# AltiumFirst_STM32.net
KiCad netlist of a schematic drawn in Altium Designer
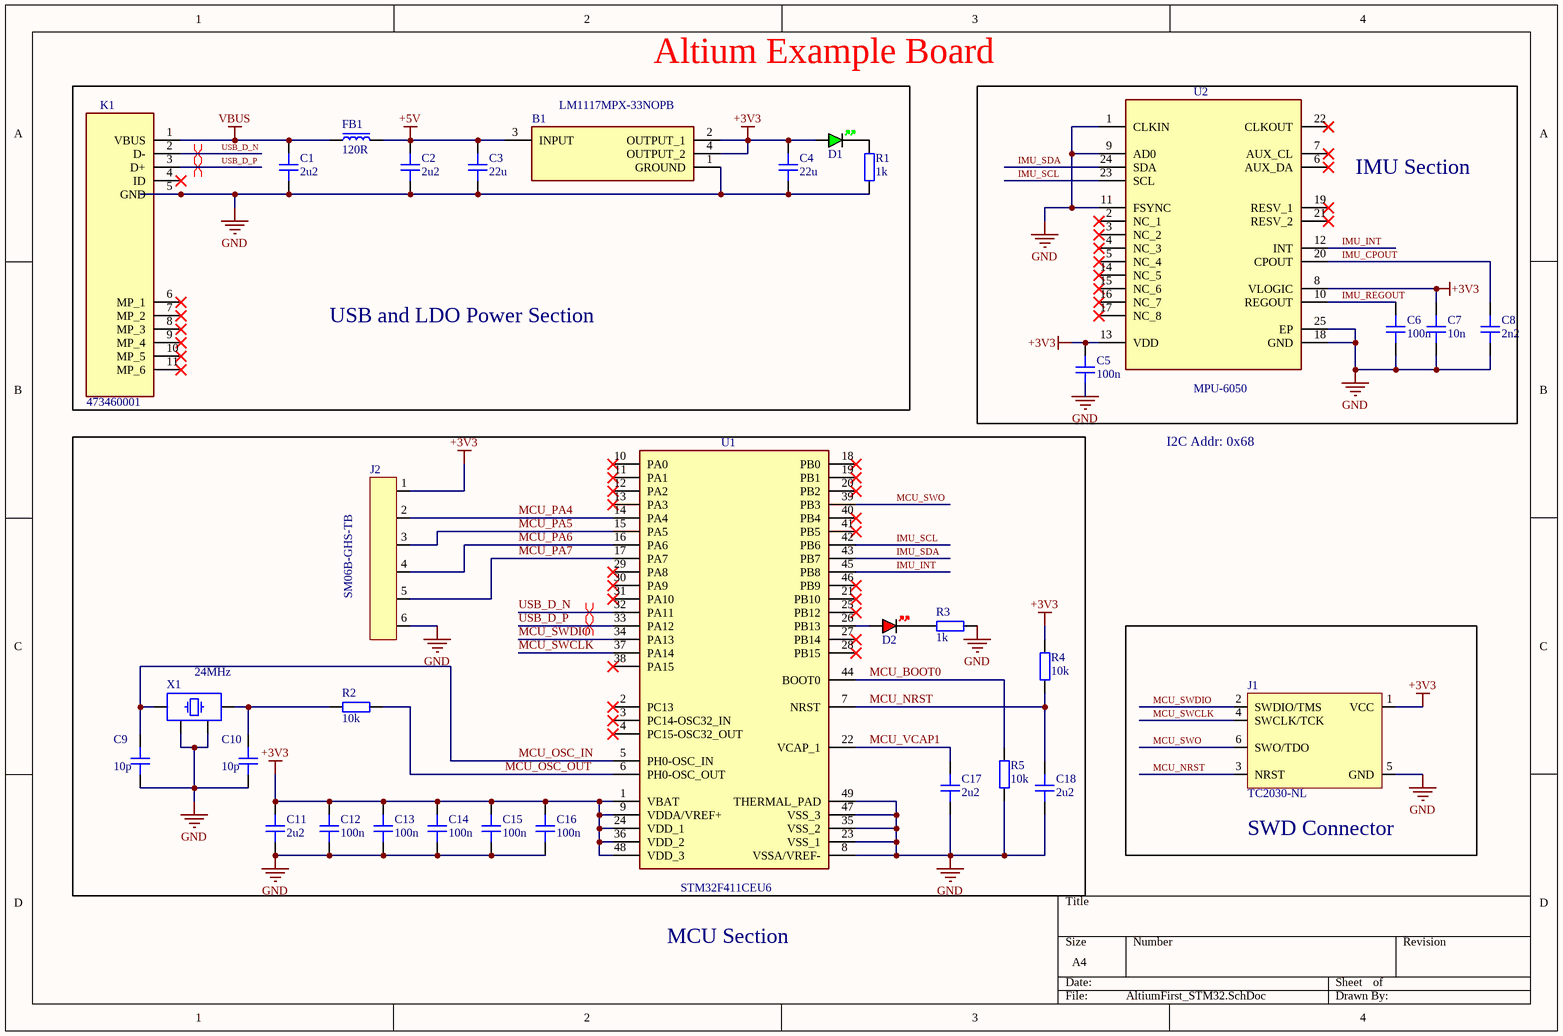
[diagram p0: AltiumFirst_STM32.SchDoc]

(export (version "E")
  (design (tool "Eeschema 10.0.6"))
  (components
    (comp (ref "B1")
      (value "LM1117MPX-33NOPB")
      (footprint "SOT230P700X180-4N")
      (fields (field (name "MOUSER PART NUMBER") "863-LM1117MPX-33NOPB"))
      (libsource (lib "LM1117MPX-33NOPB") (part "LM1117MPX-33NOPB"))
    )
    (comp (ref "C1")
      (value "2u2")
      (footprint "CAP_0603")
      (description "Capacitor SMD 0603")
      (libsource (lib "Schematic-Lib-PhilsLab") (part "CAP_0603"))
    )
    (comp (ref "C2")
      (value "2u2")
      (footprint "CAP_0603")
      (description "Capacitor SMD 0603")
      (libsource (lib "Schematic-Lib-PhilsLab") (part "CAP_0603"))
    )
    (comp (ref "C3")
      (value "22u")
      (footprint "CAP_0603")
      (description "Capacitor SMD 0603")
      (libsource (lib "Schematic-Lib-PhilsLab") (part "CAP_0603"))
    )
    (comp (ref "C4")
      (value "22u")
      (footprint "CAP_0603")
      (description "Capacitor SMD 0603")
      (libsource (lib "Schematic-Lib-PhilsLab") (part "CAP_0603"))
    )
    (comp (ref "C5")
      (value "100n")
      (footprint "CAP_0603")
      (description "Capacitor SMD 0603")
      (libsource (lib "Schematic-Lib-PhilsLab") (part "CAP_0603"))
    )
    (comp (ref "C6")
      (value "100n")
      (footprint "CAP_0603")
      (description "Capacitor SMD 0603")
      (libsource (lib "Schematic-Lib-PhilsLab") (part "CAP_0603"))
    )
    (comp (ref "C7")
      (value "10n")
      (footprint "CAP_0603")
      (description "Capacitor SMD 0603")
      (libsource (lib "Schematic-Lib-PhilsLab") (part "CAP_0603"))
    )
    (comp (ref "C8")
      (value "2n2")
      (footprint "CAP_0603")
      (description "Capacitor SMD 0603")
      (libsource (lib "Schematic-Lib-PhilsLab") (part "CAP_0603"))
    )
    (comp (ref "C9")
      (value "10p")
      (footprint "CAP_0603")
      (description "Capacitor SMD 0603")
      (libsource (lib "Schematic-Lib-PhilsLab") (part "CAP_0603"))
    )
    (comp (ref "C10")
      (value "10p")
      (footprint "CAP_0603")
      (description "Capacitor SMD 0603")
      (libsource (lib "Schematic-Lib-PhilsLab") (part "CAP_0603"))
    )
    (comp (ref "C11")
      (value "2u2")
      (footprint "CAP_0603")
      (description "Capacitor SMD 0603")
      (libsource (lib "Schematic-Lib-PhilsLab") (part "CAP_0603"))
    )
    (comp (ref "C12")
      (value "100n")
      (footprint "CAP_0603")
      (description "Capacitor SMD 0603")
      (libsource (lib "Schematic-Lib-PhilsLab") (part "CAP_0603"))
    )
    (comp (ref "C13")
      (value "100n")
      (footprint "CAP_0603")
      (description "Capacitor SMD 0603")
      (libsource (lib "Schematic-Lib-PhilsLab") (part "CAP_0603"))
    )
    (comp (ref "C14")
      (value "100n")
      (footprint "CAP_0603")
      (description "Capacitor SMD 0603")
      (libsource (lib "Schematic-Lib-PhilsLab") (part "CAP_0603"))
    )
    (comp (ref "C15")
      (value "100n")
      (footprint "CAP_0603")
      (description "Capacitor SMD 0603")
      (libsource (lib "Schematic-Lib-PhilsLab") (part "CAP_0603"))
    )
    (comp (ref "C16")
      (value "100n")
      (footprint "CAP_0603")
      (description "Capacitor SMD 0603")
      (libsource (lib "Schematic-Lib-PhilsLab") (part "CAP_0603"))
    )
    (comp (ref "C17")
      (value "2u2")
      (footprint "CAP_0603")
      (description "Capacitor SMD 0603")
      (libsource (lib "Schematic-Lib-PhilsLab") (part "CAP_0603"))
    )
    (comp (ref "C18")
      (value "2u2")
      (footprint "CAP_0603")
      (description "Capacitor SMD 0603")
      (libsource (lib "Schematic-Lib-PhilsLab") (part "CAP_0603"))
    )
    (comp (ref "D1")
      (value "GREEN")
      (footprint "LED_0603_GREEN")
      (description "LED 0603 GREEN SMD")
      (libsource (lib "Schematic-Lib-PhilsLab") (part "LED_0603_GREEN"))
    )
    (comp (ref "D2")
      (value "RED")
      (footprint "LED_0603_RED")
      (description "LED 0603 RED SMD")
      (libsource (lib "Schematic-Lib-PhilsLab") (part "LED_0603_RED"))
    )
    (comp (ref "FB1")
      (value "120R")
      (footprint "FB_0603")
      (description "Ferrite Bead SMD 0603")
      (libsource (lib "Schematic-Lib-PhilsLab") (part "FB_0603"))
    )
    (comp (ref "J1")
      (value "TC2030-NL")
      (footprint "TC2030-NL-FP")
      (description "Tag-Connect No-Solder SWD Debug Connector (No Legs) DO NOT PLACE")
      (fields
        (field (name "MANUFACTURER") "Tag-Connect")
        (field (name "MANUFACTURER PART NUMBER") "TC2030-NL-FP")
      )
      (libsource (lib "Schematic-Lib-PhilsLab") (part "TC2030-NL"))
    )
    (comp (ref "J2")
      (value "SM06B-GHS-TB")
      (footprint "SM06B-GHS-TB")
      (description "Header Connector 6 Position 1.25MM Pitch SMD Horizontal JST GH")
      (fields (field (name "MANUFACTURER") "JST"))
      (libsource (lib "Schematic-Lib-PhilsLab") (part "SM06B-GHS-TB"))
    )
    (comp (ref "K1")
      (value "473460001")
      (footprint "473460001")
      (fields
        (field (name "MOUSER PART NUMBER") "538-47346-0001")
        (field (name "MANUFACTURER_PART_NUMBER") "47346-0001")
      )
      (libsource (lib "47346-0001") (part "47346-0001"))
    )
    (comp (ref "R1")
      (value "1k")
      (footprint "RES_0603")
      (description "Resistor SMD 0603")
      (libsource (lib "Schematic-Lib-PhilsLab") (part "RES_0603"))
    )
    (comp (ref "R2")
      (value "10k")
      (footprint "RES_0603")
      (description "Resistor SMD 0603")
      (libsource (lib "Schematic-Lib-PhilsLab") (part "RES_0603"))
    )
    (comp (ref "R3")
      (value "1k")
      (footprint "RES_0603")
      (description "Resistor SMD 0603")
      (libsource (lib "Schematic-Lib-PhilsLab") (part "RES_0603"))
    )
    (comp (ref "R4")
      (value "10k")
      (footprint "RES_0603")
      (description "Resistor SMD 0603")
      (libsource (lib "Schematic-Lib-PhilsLab") (part "RES_0603"))
    )
    (comp (ref "R5")
      (value "10k")
      (footprint "RES_0603")
      (description "Resistor SMD 0603")
      (libsource (lib "Schematic-Lib-PhilsLab") (part "RES_0603"))
    )
    (comp (ref "U1")
      (value "STM32F411CEU6")
      (footprint "QFN50P700X700X60-49N-D")
      (fields (field (name "MOUSER PART NUMBER") "511-STM32F411CEU6"))
      (libsource (lib "STM32F411CEU6") (part "STM32F411CEU6"))
    )
    (comp (ref "U2")
      (value "MPU-6050")
      (footprint "MPU6050")
      (description "IMUs - Inertial Measurement Units 6-Axis MEMS MotionTracking  Device with DMP")
      (fields (field (name "MOUSER PART NUMBER") "410-MPU-6050"))
      (libsource (lib "MPU-6050") (part "MPU-6050"))
    )
    (comp (ref "X1")
      (value "24MHz")
      (footprint "XTAL_3225")
      (description "Crystal SMD 24MHz 10PPM 7pF 3225")
      (fields
        (field (name "MANUFACTURER") "Epson")
        (field (name "MANUFACTURER PART NUMBER") "TSX-3225 24.0000MF15X-AC")
      )
      (libsource (lib "Schematic-Lib-PhilsLab") (part "TSX-3225_24.0000MF15X-AC"))
    )
  )
  (nets
    (net (code "1") (name "+3V3") (class "Default")
      (node (ref "B1") (pin "2") (pinfunction "OUTPUT_1_2") (pintype "passive"))
      (node (ref "B1") (pin "4") (pinfunction "OUTPUT_2_4") (pintype "passive"))
      (node (ref "C11") (pin "2") (pinfunction "2_2") (pintype "passive"))
      (node (ref "C12") (pin "2") (pinfunction "2_2") (pintype "passive"))
      (node (ref "C13") (pin "2") (pinfunction "2_2") (pintype "passive"))
      (node (ref "C14") (pin "2") (pinfunction "2_2") (pintype "passive"))
      (node (ref "C15") (pin "2") (pinfunction "2_2") (pintype "passive"))
      (node (ref "C16") (pin "2") (pinfunction "2_2") (pintype "passive"))
      (node (ref "C4") (pin "2") (pinfunction "2_2") (pintype "passive"))
      (node (ref "C5") (pin "2") (pinfunction "2_2") (pintype "passive"))
      (node (ref "C7") (pin "2") (pinfunction "2_2") (pintype "passive"))
      (node (ref "D1") (pin "A") (pinfunction "A_A") (pintype "passive"))
      (node (ref "J1") (pin "1") (pinfunction "VCC_1") (pintype "passive"))
      (node (ref "J2") (pin "1") (pinfunction "1_1") (pintype "passive"))
      (node (ref "R4") (pin "2") (pinfunction "2_2") (pintype "passive"))
      (node (ref "U1") (pin "1") (pinfunction "VBAT_1") (pintype "passive"))
      (node (ref "U1") (pin "24") (pinfunction "VDD_1_24") (pintype "passive"))
      (node (ref "U1") (pin "36") (pinfunction "VDD_2_36") (pintype "passive"))
      (node (ref "U1") (pin "48") (pinfunction "VDD_3_48") (pintype "passive"))
      (node (ref "U1") (pin "9") (pinfunction "VDDA/VREF+_9") (pintype "passive"))
      (node (ref "U2") (pin "13") (pinfunction "VDD_13") (pintype "passive"))
      (node (ref "U2") (pin "8") (pinfunction "VLOGIC_8") (pintype "passive"))
    )
    (net (code "2") (name "+5V") (class "Default")
      (node (ref "B1") (pin "3") (pinfunction "INPUT_3") (pintype "passive"))
      (node (ref "C2") (pin "2") (pinfunction "2_2") (pintype "passive"))
      (node (ref "C3") (pin "2") (pinfunction "2_2") (pintype "passive"))
      (node (ref "FB1") (pin "2") (pinfunction "2_2") (pintype "passive"))
    )
    (net (code "3") (name "/IMU_CPOUT") (class "Default")
      (node (ref "C8") (pin "2") (pinfunction "2_2") (pintype "passive"))
      (node (ref "U2") (pin "20") (pinfunction "CPOUT_20") (pintype "passive"))
    )
    (net (code "4") (name "/IMU_INT") (class "Default")
      (node (ref "U1") (pin "45") (pinfunction "PB8_45") (pintype "passive"))
      (node (ref "U2") (pin "12") (pinfunction "INT_12") (pintype "passive"))
    )
    (net (code "5") (name "/IMU_REGOUT") (class "Default")
      (node (ref "C6") (pin "2") (pinfunction "2_2") (pintype "passive"))
      (node (ref "U2") (pin "10") (pinfunction "REGOUT_10") (pintype "passive"))
    )
    (net (code "6") (name "/IMU_SCL") (class "Default")
      (node (ref "U1") (pin "42") (pinfunction "PB6_42") (pintype "passive"))
      (node (ref "U2") (pin "23") (pinfunction "SCL_23") (pintype "passive"))
    )
    (net (code "7") (name "/IMU_SDA") (class "Default")
      (node (ref "U1") (pin "43") (pinfunction "PB7_43") (pintype "passive"))
      (node (ref "U2") (pin "24") (pinfunction "SDA_24") (pintype "passive"))
    )
    (net (code "8") (name "/MCU_BOOT0") (class "Default")
      (node (ref "R5") (pin "2") (pinfunction "2_2") (pintype "passive"))
      (node (ref "U1") (pin "44") (pinfunction "BOOT0_44") (pintype "passive"))
    )
    (net (code "9") (name "/MCU_NRST") (class "Default")
      (node (ref "C18") (pin "2") (pinfunction "2_2") (pintype "passive"))
      (node (ref "J1") (pin "3") (pinfunction "NRST_3") (pintype "passive"))
      (node (ref "R4") (pin "1") (pinfunction "1_1") (pintype "passive"))
      (node (ref "U1") (pin "7") (pinfunction "NRST_7") (pintype "passive"))
    )
    (net (code "10") (name "/MCU_OSC_IN") (class "Default")
      (node (ref "C9") (pin "2") (pinfunction "2_2") (pintype "passive"))
      (node (ref "U1") (pin "5") (pinfunction "PH0-OSC_IN_5") (pintype "passive"))
      (node (ref "X1") (pin "1") (pinfunction "1_1") (pintype "passive"))
    )
    (net (code "11") (name "/MCU_OSC_OUT") (class "Default")
      (node (ref "R2") (pin "1") (pinfunction "1_1") (pintype "passive"))
      (node (ref "U1") (pin "6") (pinfunction "PH0-OSC_OUT_6") (pintype "passive"))
    )
    (net (code "12") (name "/MCU_PA4") (class "Default")
      (node (ref "J2") (pin "2") (pinfunction "2_2") (pintype "passive"))
      (node (ref "U1") (pin "14") (pinfunction "PA4_14") (pintype "passive"))
    )
    (net (code "13") (name "/MCU_PA5") (class "Default")
      (node (ref "J2") (pin "3") (pinfunction "3_3") (pintype "passive"))
      (node (ref "U1") (pin "15") (pinfunction "PA5_15") (pintype "passive"))
    )
    (net (code "14") (name "/MCU_PA6") (class "Default")
      (node (ref "J2") (pin "4") (pinfunction "4_4") (pintype "passive"))
      (node (ref "U1") (pin "16") (pinfunction "PA6_16") (pintype "passive"))
    )
    (net (code "15") (name "/MCU_PA7") (class "Default")
      (node (ref "J2") (pin "5") (pinfunction "5_5") (pintype "passive"))
      (node (ref "U1") (pin "17") (pinfunction "PA7_17") (pintype "passive"))
    )
    (net (code "16") (name "/MCU_SWCLK") (class "Default")
      (node (ref "J1") (pin "4") (pinfunction "SWCLK/TCK_4") (pintype "passive"))
      (node (ref "U1") (pin "37") (pinfunction "PA14_37") (pintype "passive"))
    )
    (net (code "17") (name "/MCU_SWDIO") (class "Default")
      (node (ref "J1") (pin "2") (pinfunction "SWDIO/TMS_2") (pintype "passive"))
      (node (ref "U1") (pin "34") (pinfunction "PA13_34") (pintype "passive"))
    )
    (net (code "18") (name "/MCU_SWO") (class "Default")
      (node (ref "J1") (pin "6") (pinfunction "SWO/TDO_6") (pintype "passive"))
      (node (ref "U1") (pin "39") (pinfunction "PB3_39") (pintype "passive"))
    )
    (net (code "19") (name "/MCU_VCAP1") (class "Default")
      (node (ref "C17") (pin "2") (pinfunction "2_2") (pintype "passive"))
      (node (ref "U1") (pin "22") (pinfunction "VCAP_1_22") (pintype "passive"))
    )
    (net (code "20") (name "/USB_D_N") (class "Default")
      (node (ref "K1") (pin "2") (pinfunction "D-_2") (pintype "passive"))
      (node (ref "U1") (pin "32") (pinfunction "PA11_32") (pintype "passive"))
    )
    (net (code "21") (name "/USB_D_P") (class "Default")
      (node (ref "K1") (pin "3") (pinfunction "D+_3") (pintype "passive"))
      (node (ref "U1") (pin "33") (pinfunction "PA12_33") (pintype "passive"))
    )
    (net (code "22") (name "GND") (class "Default")
      (node (ref "B1") (pin "1") (pinfunction "GROUND_1") (pintype "passive"))
      (node (ref "C1") (pin "1") (pinfunction "1_1") (pintype "passive"))
      (node (ref "C10") (pin "1") (pinfunction "1_1") (pintype "passive"))
      (node (ref "C11") (pin "1") (pinfunction "1_1") (pintype "passive"))
      (node (ref "C12") (pin "1") (pinfunction "1_1") (pintype "passive"))
      (node (ref "C13") (pin "1") (pinfunction "1_1") (pintype "passive"))
      (node (ref "C14") (pin "1") (pinfunction "1_1") (pintype "passive"))
      (node (ref "C15") (pin "1") (pinfunction "1_1") (pintype "passive"))
      (node (ref "C16") (pin "1") (pinfunction "1_1") (pintype "passive"))
      (node (ref "C17") (pin "1") (pinfunction "1_1") (pintype "passive"))
      (node (ref "C18") (pin "1") (pinfunction "1_1") (pintype "passive"))
      (node (ref "C2") (pin "1") (pinfunction "1_1") (pintype "passive"))
      (node (ref "C3") (pin "1") (pinfunction "1_1") (pintype "passive"))
      (node (ref "C4") (pin "1") (pinfunction "1_1") (pintype "passive"))
      (node (ref "C5") (pin "1") (pinfunction "1_1") (pintype "passive"))
      (node (ref "C6") (pin "1") (pinfunction "1_1") (pintype "passive"))
      (node (ref "C7") (pin "1") (pinfunction "1_1") (pintype "passive"))
      (node (ref "C8") (pin "1") (pinfunction "1_1") (pintype "passive"))
      (node (ref "C9") (pin "1") (pinfunction "1_1") (pintype "passive"))
      (node (ref "J1") (pin "5") (pinfunction "GND_5") (pintype "passive"))
      (node (ref "J2") (pin "6") (pinfunction "6_6") (pintype "passive"))
      (node (ref "K1") (pin "5") (pinfunction "GND_5") (pintype "passive"))
      (node (ref "R1") (pin "1") (pinfunction "1_1") (pintype "passive"))
      (node (ref "R3") (pin "1") (pinfunction "1_1") (pintype "passive"))
      (node (ref "R5") (pin "1") (pinfunction "1_1") (pintype "passive"))
      (node (ref "U1") (pin "23") (pinfunction "VSS_1_23") (pintype "passive"))
      (node (ref "U1") (pin "35") (pinfunction "VSS_2_35") (pintype "passive"))
      (node (ref "U1") (pin "47") (pinfunction "VSS_3_47") (pintype "passive"))
      (node (ref "U1") (pin "49") (pinfunction "THERMAL_PAD_49") (pintype "passive"))
      (node (ref "U1") (pin "8") (pinfunction "VSSA/VREF-_8") (pintype "passive"))
      (node (ref "U2") (pin "1") (pinfunction "CLKIN_1") (pintype "passive"))
      (node (ref "U2") (pin "11") (pinfunction "FSYNC_11") (pintype "passive"))
      (node (ref "U2") (pin "18") (pinfunction "GND_18") (pintype "passive"))
      (node (ref "U2") (pin "25") (pinfunction "EP_25") (pintype "passive"))
      (node (ref "U2") (pin "9") (pinfunction "AD0_9") (pintype "passive"))
      (node (ref "X1") (pin "2") (pinfunction "2_2") (pintype "passive"))
      (node (ref "X1") (pin "4") (pinfunction "4_4") (pintype "passive"))
    )
    (net (code "23") (name "Net-(C10-Pad2)") (class "Default")
      (node (ref "C10") (pin "2") (pinfunction "2_2") (pintype "passive"))
      (node (ref "R2") (pin "2") (pinfunction "2_2") (pintype "passive"))
      (node (ref "X1") (pin "3") (pinfunction "3_3") (pintype "passive"))
    )
    (net (code "24") (name "Net-(D1-PadK)") (class "Default")
      (node (ref "D1") (pin "K") (pinfunction "K_K") (pintype "passive"))
      (node (ref "R1") (pin "2") (pinfunction "2_2") (pintype "passive"))
    )
    (net (code "25") (name "Net-(D2-PadK)") (class "Default")
      (node (ref "D2") (pin "K") (pinfunction "K_K") (pintype "passive"))
      (node (ref "R3") (pin "2") (pinfunction "2_2") (pintype "passive"))
    )
    (net (code "26") (name "Net-(U1-PB13)") (class "Default")
      (node (ref "D2") (pin "A") (pinfunction "A_A") (pintype "passive"))
      (node (ref "U1") (pin "26") (pinfunction "PB13_26") (pintype "passive"))
    )
    (net (code "27") (name "VBUS") (class "Default")
      (node (ref "C1") (pin "2") (pinfunction "2_2") (pintype "passive"))
      (node (ref "FB1") (pin "1") (pinfunction "1_1") (pintype "passive"))
      (node (ref "K1") (pin "1") (pinfunction "VBUS_1") (pintype "passive"))
    )
    (net (code "28") (name "unconnected-(K1-ID-Pad4)") (class "Default")
      (node (ref "K1") (pin "4") (pinfunction "ID_4") (pintype "passive+no_connect"))
    )
    (net (code "29") (name "unconnected-(K1-MP_1-Pad6)") (class "Default")
      (node (ref "K1") (pin "6") (pinfunction "MP_1_6") (pintype "passive+no_connect"))
    )
    (net (code "30") (name "unconnected-(K1-MP_2-Pad7)") (class "Default")
      (node (ref "K1") (pin "7") (pinfunction "MP_2_7") (pintype "passive+no_connect"))
    )
    (net (code "31") (name "unconnected-(K1-MP_3-Pad8)") (class "Default")
      (node (ref "K1") (pin "8") (pinfunction "MP_3_8") (pintype "passive+no_connect"))
    )
    (net (code "32") (name "unconnected-(K1-MP_4-Pad9)") (class "Default")
      (node (ref "K1") (pin "9") (pinfunction "MP_4_9") (pintype "passive+no_connect"))
    )
    (net (code "33") (name "unconnected-(K1-MP_5-Pad10)") (class "Default")
      (node (ref "K1") (pin "10") (pinfunction "MP_5_10") (pintype "passive+no_connect"))
    )
    (net (code "34") (name "unconnected-(K1-MP_6-Pad11)") (class "Default")
      (node (ref "K1") (pin "11") (pinfunction "MP_6_11") (pintype "passive+no_connect"))
    )
    (net (code "35") (name "unconnected-(U1-PA0-Pad10)") (class "Default")
      (node (ref "U1") (pin "10") (pinfunction "PA0_10") (pintype "passive+no_connect"))
    )
    (net (code "36") (name "unconnected-(U1-PA1-Pad11)") (class "Default")
      (node (ref "U1") (pin "11") (pinfunction "PA1_11") (pintype "passive+no_connect"))
    )
    (net (code "37") (name "unconnected-(U1-PA2-Pad12)") (class "Default")
      (node (ref "U1") (pin "12") (pinfunction "PA2_12") (pintype "passive+no_connect"))
    )
    (net (code "38") (name "unconnected-(U1-PA3-Pad13)") (class "Default")
      (node (ref "U1") (pin "13") (pinfunction "PA3_13") (pintype "passive+no_connect"))
    )
    (net (code "39") (name "unconnected-(U1-PA8-Pad29)") (class "Default")
      (node (ref "U1") (pin "29") (pinfunction "PA8_29") (pintype "passive+no_connect"))
    )
    (net (code "40") (name "unconnected-(U1-PA9-Pad30)") (class "Default")
      (node (ref "U1") (pin "30") (pinfunction "PA9_30") (pintype "passive+no_connect"))
    )
    (net (code "41") (name "unconnected-(U1-PA10-Pad31)") (class "Default")
      (node (ref "U1") (pin "31") (pinfunction "PA10_31") (pintype "passive+no_connect"))
    )
    (net (code "42") (name "unconnected-(U1-PA15-Pad38)") (class "Default")
      (node (ref "U1") (pin "38") (pinfunction "PA15_38") (pintype "passive+no_connect"))
    )
    (net (code "43") (name "unconnected-(U1-PB0-Pad18)") (class "Default")
      (node (ref "U1") (pin "18") (pinfunction "PB0_18") (pintype "passive+no_connect"))
    )
    (net (code "44") (name "unconnected-(U1-PB1-Pad19)") (class "Default")
      (node (ref "U1") (pin "19") (pinfunction "PB1_19") (pintype "passive+no_connect"))
    )
    (net (code "45") (name "unconnected-(U1-PB2-Pad20)") (class "Default")
      (node (ref "U1") (pin "20") (pinfunction "PB2_20") (pintype "passive+no_connect"))
    )
    (net (code "46") (name "unconnected-(U1-PB4-Pad40)") (class "Default")
      (node (ref "U1") (pin "40") (pinfunction "PB4_40") (pintype "passive+no_connect"))
    )
    (net (code "47") (name "unconnected-(U1-PB5-Pad41)") (class "Default")
      (node (ref "U1") (pin "41") (pinfunction "PB5_41") (pintype "passive+no_connect"))
    )
    (net (code "48") (name "unconnected-(U1-PB9-Pad46)") (class "Default")
      (node (ref "U1") (pin "46") (pinfunction "PB9_46") (pintype "passive+no_connect"))
    )
    (net (code "49") (name "unconnected-(U1-PB10-Pad21)") (class "Default")
      (node (ref "U1") (pin "21") (pinfunction "PB10_21") (pintype "passive+no_connect"))
    )
    (net (code "50") (name "unconnected-(U1-PB12-Pad25)") (class "Default")
      (node (ref "U1") (pin "25") (pinfunction "PB12_25") (pintype "passive+no_connect"))
    )
    (net (code "51") (name "unconnected-(U1-PB14-Pad27)") (class "Default")
      (node (ref "U1") (pin "27") (pinfunction "PB14_27") (pintype "passive+no_connect"))
    )
    (net (code "52") (name "unconnected-(U1-PB15-Pad28)") (class "Default")
      (node (ref "U1") (pin "28") (pinfunction "PB15_28") (pintype "passive+no_connect"))
    )
    (net (code "53") (name "unconnected-(U1-PC13-Pad2)") (class "Default")
      (node (ref "U1") (pin "2") (pinfunction "PC13_2") (pintype "passive+no_connect"))
    )
    (net (code "54") (name "unconnected-(U1-PC14-OSC32_IN-Pad3)") (class "Default")
      (node (ref "U1") (pin "3") (pinfunction "PC14-OSC32_IN_3") (pintype "passive+no_connect"))
    )
    (net (code "55") (name "unconnected-(U1-PC15-OSC32_OUT-Pad4)") (class "Default")
      (node (ref "U1") (pin "4") (pinfunction "PC15-OSC32_OUT_4") (pintype "passive+no_connect"))
    )
    (net (code "56") (name "unconnected-(U2-AUX_CL-Pad7)") (class "Default")
      (node (ref "U2") (pin "7") (pinfunction "AUX_CL_7") (pintype "passive+no_connect"))
    )
    (net (code "57") (name "unconnected-(U2-AUX_DA-Pad6)") (class "Default")
      (node (ref "U2") (pin "6") (pinfunction "AUX_DA_6") (pintype "passive+no_connect"))
    )
    (net (code "58") (name "unconnected-(U2-CLKOUT-Pad22)") (class "Default")
      (node (ref "U2") (pin "22") (pinfunction "CLKOUT_22") (pintype "passive+no_connect"))
    )
    (net (code "59") (name "unconnected-(U2-NC_1-Pad2)") (class "Default")
      (node (ref "U2") (pin "2") (pinfunction "NC_1_2") (pintype "passive+no_connect"))
    )
    (net (code "60") (name "unconnected-(U2-NC_2-Pad3)") (class "Default")
      (node (ref "U2") (pin "3") (pinfunction "NC_2_3") (pintype "passive+no_connect"))
    )
    (net (code "61") (name "unconnected-(U2-NC_3-Pad4)") (class "Default")
      (node (ref "U2") (pin "4") (pinfunction "NC_3_4") (pintype "passive+no_connect"))
    )
    (net (code "62") (name "unconnected-(U2-NC_4-Pad5)") (class "Default")
      (node (ref "U2") (pin "5") (pinfunction "NC_4_5") (pintype "passive+no_connect"))
    )
    (net (code "63") (name "unconnected-(U2-NC_5-Pad14)") (class "Default")
      (node (ref "U2") (pin "14") (pinfunction "NC_5_14") (pintype "passive+no_connect"))
    )
    (net (code "64") (name "unconnected-(U2-NC_6-Pad15)") (class "Default")
      (node (ref "U2") (pin "15") (pinfunction "NC_6_15") (pintype "passive+no_connect"))
    )
    (net (code "65") (name "unconnected-(U2-NC_7-Pad16)") (class "Default")
      (node (ref "U2") (pin "16") (pinfunction "NC_7_16") (pintype "passive+no_connect"))
    )
    (net (code "66") (name "unconnected-(U2-NC_8-Pad17)") (class "Default")
      (node (ref "U2") (pin "17") (pinfunction "NC_8_17") (pintype "passive+no_connect"))
    )
    (net (code "67") (name "unconnected-(U2-RESV_1-Pad19)") (class "Default")
      (node (ref "U2") (pin "19") (pinfunction "RESV_1_19") (pintype "passive+no_connect"))
    )
    (net (code "68") (name "unconnected-(U2-RESV_2-Pad21)") (class "Default")
      (node (ref "U2") (pin "21") (pinfunction "RESV_2_21") (pintype "passive+no_connect"))
    )
  )
)
